# Fuse.net
KiCad netlist of a schematic drawn in EAGLE
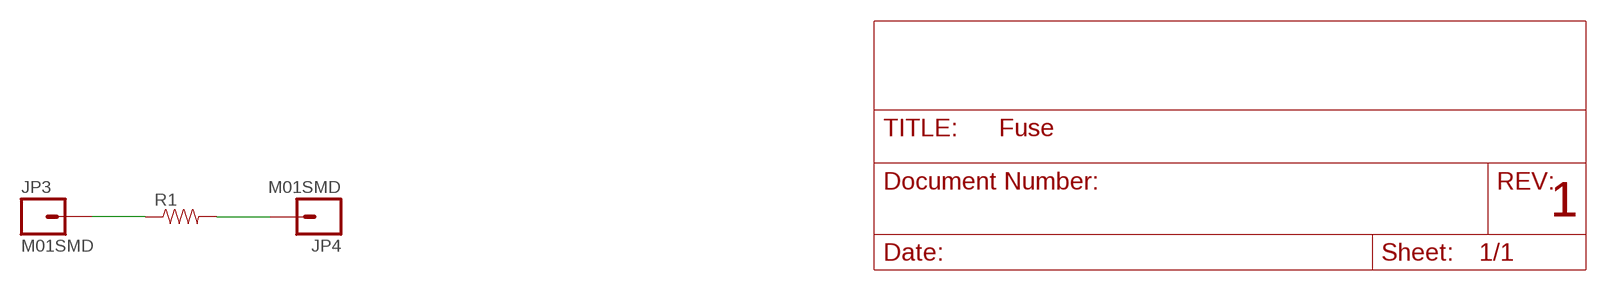
[diagram p0: schematic, sheet 1]

(export (version "E")
  (design (tool "Eeschema 10.0.6"))
  (components
    (comp (ref "JP3")
      (value "M01SMD")
      (footprint "eagle-import:LUXEON-PAD")
      (libsource (lib "eagle-import") (part "M01SMD"))
    )
    (comp (ref "JP4")
      (value "M01SMD")
      (footprint "eagle-import:LUXEON-PAD")
      (libsource (lib "eagle-import") (part "M01SMD"))
    )
    (comp (ref "R1")
      (value "RESISTOR1206")
      (footprint "eagle-import:1206")
      (libsource (lib "eagle-import") (part "RESISTOR1206"))
    )
  )
  (nets
    (net (code "1") (name "Net-(JP3-1)") (class "Default")
      (node (ref "JP3") (pin "P$1") (pinfunction "1_P$1") (pintype "passive"))
      (node (ref "R1") (pin "1") (pinfunction "1_1") (pintype "passive"))
    )
    (net (code "2") (name "Net-(JP4-1)") (class "Default")
      (node (ref "JP4") (pin "P$1") (pinfunction "1_P$1") (pintype "passive"))
      (node (ref "R1") (pin "2") (pinfunction "2_2") (pintype "passive"))
    )
  )
)
